# Cannabis_Humidity_2021-02-28.net
KiCad netlist of a schematic drawn in EasyEDA
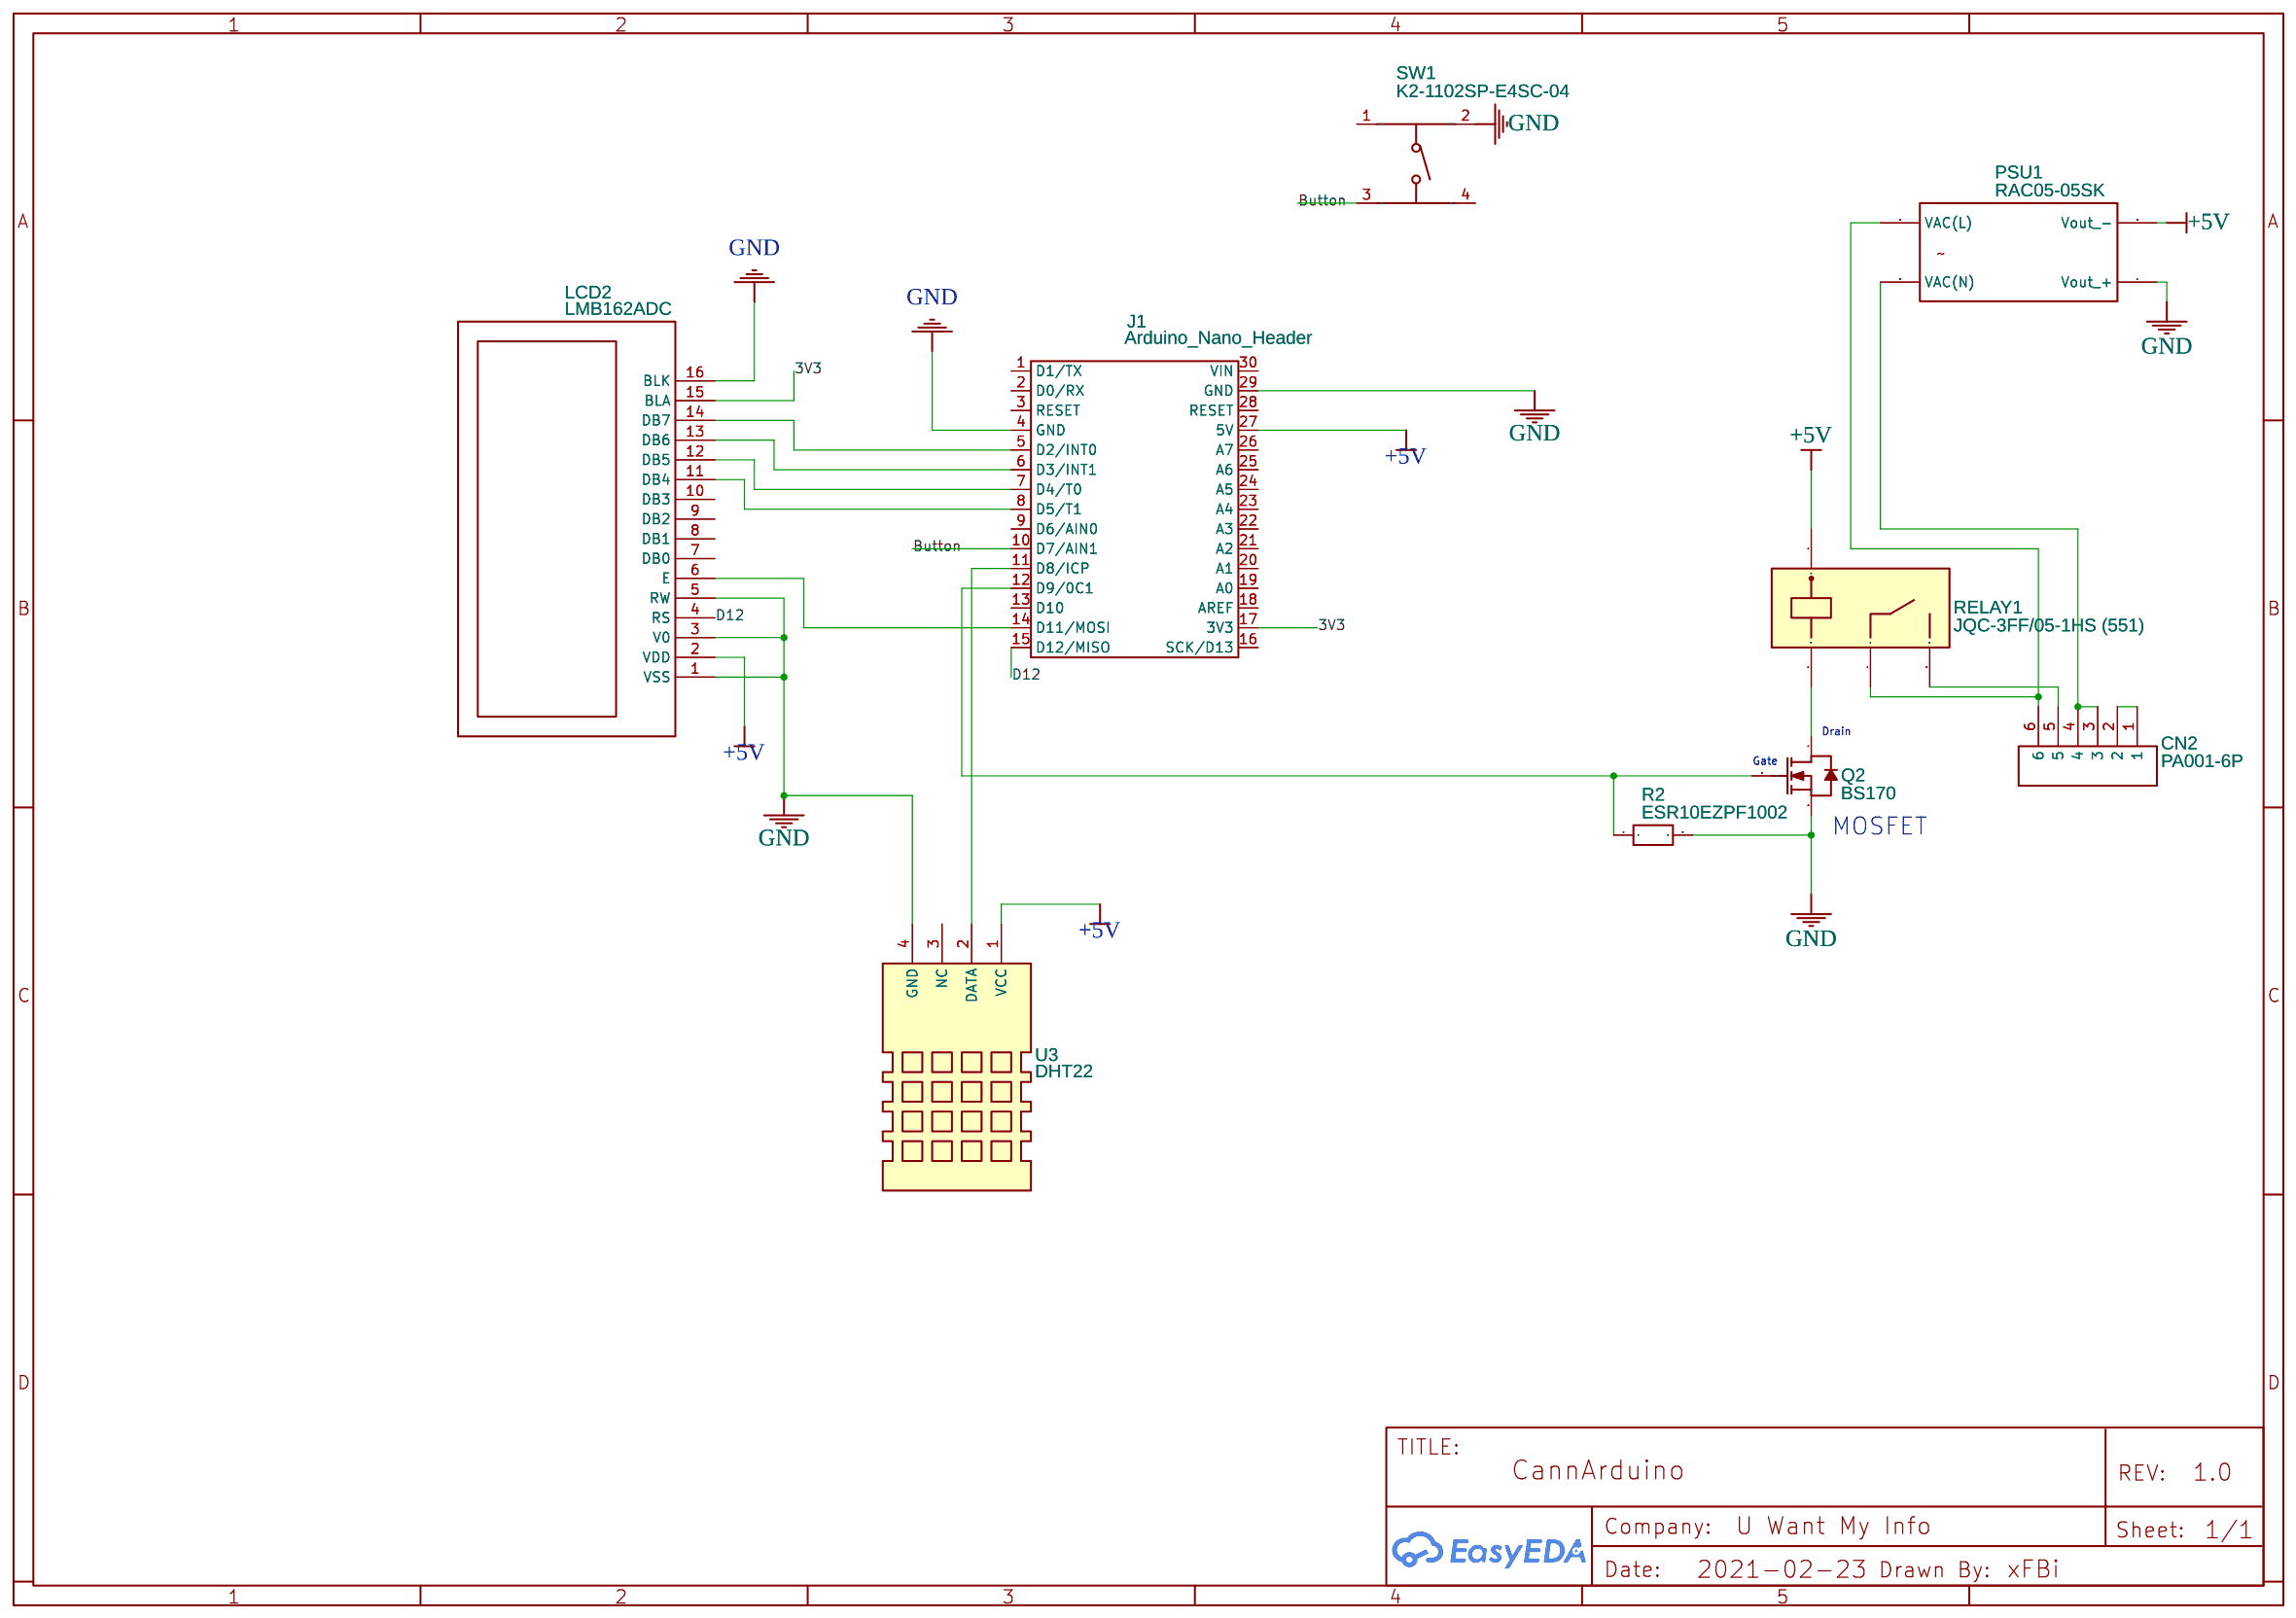
[diagram p0: schematic sheet]

(export (version "E")
  (design (tool "Eeschema 10.0.6"))
  (components
    (comp (ref "CN2")
      (value "PA001-6P")
      (fields (field (name "BOM_Supplier Part") "C173288"))
      (libsource (lib "") (part "PA001-6P"))
    )
    (comp (ref "J1") (value "Arduino_Nano_Header") (libsource (lib "") (part "Arduino_Nano_Header")))
    (comp (ref "LCD2")
      (value "LMB162ADC")
      (fields (field (name "BOM_Supplier Part") "C9741"))
      (libsource (lib "") (part "LMB162ADC"))
    )
    (comp (ref "PSU1")
      (value "RAC05-05SK")
      (fields (field (name "BOM_Supplier Part") "919-RAC05-05SK"))
      (libsource (lib "") (part "RAC05-05SK"))
    )
    (comp (ref "Q2")
      (value "BS170")
      (fields (field (name "BOM_Supplier Part") "C111691"))
      (libsource (lib "") (part "BS170"))
    )
    (comp (ref "R2")
      (value "ESR10EZPF1002")
      (fields (field (name "BOM_Supplier Part") "C510098"))
      (libsource (lib "") (part "ESR10EZPF1002"))
    )
    (comp (ref "RELAY1")
      (value "JQC-3FF/05-1HS (551)")
      (fields (field (name "BOM_Supplier Part") "C9224"))
      (libsource (lib "") (part "JQC-3FF/05-1HS (551)"))
    )
    (comp (ref "SW1")
      (value "K2-1102SP-E4SC-04")
      (fields (field (name "BOM_Supplier Part") "C136669"))
      (libsource (lib "") (part "K2-1102SP-E4SC-04"))
    )
    (comp (ref "U3")
      (value "DHT22")
      (fields (field (name "BOM_Supplier Part") "PRODUCT ID: 385"))
      (libsource (lib "") (part "DHT22"))
    )
  )
  (nets
    (net (code "1") (name "+5V") (class "Default")
      (node (ref "J1") (pin "27") (pinfunction "5V_27") (pintype "unspecified"))
      (node (ref "LCD2") (pin "2") (pinfunction "VDD_2") (pintype "unspecified"))
      (node (ref "PSU1") (pin "5") (pinfunction "Vout_-_5") (pintype "output"))
      (node (ref "RELAY1") (pin "1") (pinfunction "1_1") (pintype "input"))
      (node (ref "U3") (pin "1") (pinfunction "VCC_1") (pintype "unspecified"))
    )
    (net (code "2") (name "/3V3") (class "Default")
      (node (ref "J1") (pin "17") (pinfunction "3V3_17") (pintype "unspecified"))
      (node (ref "LCD2") (pin "15") (pinfunction "BLA_15") (pintype "unspecified"))
    )
    (net (code "3") (name "/Button") (class "Default")
      (node (ref "J1") (pin "10") (pinfunction "D7/AIN1_10") (pintype "unspecified"))
      (node (ref "SW1") (pin "3") (pinfunction "3_3") (pintype "unspecified"))
    )
    (net (code "4") (name "/D12") (class "Default")
      (node (ref "J1") (pin "15") (pinfunction "D12/MISO_15") (pintype "unspecified"))
      (node (ref "LCD2") (pin "4") (pinfunction "RS_4") (pintype "unspecified"))
    )
    (net (code "5") (name "GND") (class "Default")
      (node (ref "J1") (pin "29") (pinfunction "GND_29") (pintype "unspecified"))
      (node (ref "J1") (pin "4") (pinfunction "GND_4") (pintype "unspecified"))
      (node (ref "LCD2") (pin "1") (pinfunction "VSS_1") (pintype "unspecified"))
      (node (ref "LCD2") (pin "16") (pinfunction "BLK_16") (pintype "unspecified"))
      (node (ref "LCD2") (pin "3") (pinfunction "V0_3") (pintype "unspecified"))
      (node (ref "LCD2") (pin "5") (pinfunction "RW_5") (pintype "unspecified"))
      (node (ref "PSU1") (pin "4") (pinfunction "Vout_+_4") (pintype "output"))
      (node (ref "Q2") (pin "3") (pinfunction "S_3") (pintype "unspecified"))
      (node (ref "R2") (pin "2") (pinfunction "2_2") (pintype "unspecified"))
      (node (ref "SW1") (pin "2") (pinfunction "2_2") (pintype "unspecified"))
      (node (ref "U3") (pin "4") (pinfunction "GND_4") (pintype "unspecified"))
    )
    (net (code "6") (name "Net-(CN2-Pad1)") (class "Default")
      (node (ref "CN2") (pin "1") (pinfunction "1_1") (pintype "unspecified"))
      (node (ref "CN2") (pin "2") (pinfunction "2_2") (pintype "unspecified"))
    )
    (net (code "7") (name "Net-(CN2-Pad5)") (class "Default")
      (node (ref "CN2") (pin "5") (pinfunction "5_5") (pintype "unspecified"))
      (node (ref "RELAY1") (pin "3") (pinfunction "3_3") (pintype "input"))
    )
    (net (code "8") (name "Net-(J1-D2{slash}INT0)") (class "Default")
      (node (ref "J1") (pin "5") (pinfunction "D2/INT0_5") (pintype "unspecified"))
      (node (ref "LCD2") (pin "14") (pinfunction "DB7_14") (pintype "unspecified"))
    )
    (net (code "9") (name "Net-(J1-D3{slash}INT1)") (class "Default")
      (node (ref "J1") (pin "6") (pinfunction "D3/INT1_6") (pintype "unspecified"))
      (node (ref "LCD2") (pin "13") (pinfunction "DB6_13") (pintype "unspecified"))
    )
    (net (code "10") (name "Net-(J1-D4{slash}T0)") (class "Default")
      (node (ref "J1") (pin "7") (pinfunction "D4/T0_7") (pintype "unspecified"))
      (node (ref "LCD2") (pin "12") (pinfunction "DB5_12") (pintype "unspecified"))
    )
    (net (code "11") (name "Net-(J1-D5{slash}T1)") (class "Default")
      (node (ref "J1") (pin "8") (pinfunction "D5/T1_8") (pintype "unspecified"))
      (node (ref "LCD2") (pin "11") (pinfunction "DB4_11") (pintype "unspecified"))
    )
    (net (code "12") (name "Net-(J1-D8{slash}ICP)") (class "Default")
      (node (ref "J1") (pin "11") (pinfunction "D8/ICP_11") (pintype "unspecified"))
      (node (ref "U3") (pin "2") (pinfunction "DATA_2") (pintype "unspecified"))
    )
    (net (code "13") (name "Net-(J1-D9{slash}0C1)") (class "Default")
      (node (ref "J1") (pin "12") (pinfunction "D9/0C1_12") (pintype "unspecified"))
      (node (ref "Q2") (pin "2") (pinfunction "G_2") (pintype "unspecified"))
      (node (ref "R2") (pin "1") (pinfunction "1_1") (pintype "unspecified"))
    )
    (net (code "14") (name "Net-(J1-D11{slash}MOSI)") (class "Default")
      (node (ref "J1") (pin "14") (pinfunction "D11/MOSI_14") (pintype "unspecified"))
      (node (ref "LCD2") (pin "6") (pinfunction "E_6") (pintype "unspecified"))
    )
    (net (code "15") (name "Net-(PSU1-VAC(L))") (class "Default")
      (node (ref "CN2") (pin "6") (pinfunction "6_6") (pintype "unspecified"))
      (node (ref "PSU1") (pin "1") (pinfunction "VAC(L)_1") (pintype "input"))
      (node (ref "RELAY1") (pin "4") (pinfunction "4_4") (pintype "input"))
    )
    (net (code "16") (name "Net-(PSU1-VAC(N))") (class "Default")
      (node (ref "CN2") (pin "3") (pinfunction "3_3") (pintype "unspecified"))
      (node (ref "CN2") (pin "4") (pinfunction "4_4") (pintype "unspecified"))
      (node (ref "PSU1") (pin "2") (pinfunction "VAC(N)_2") (pintype "input"))
    )
    (net (code "17") (name "Net-(Q2-D)") (class "Default")
      (node (ref "Q2") (pin "1") (pinfunction "D_1") (pintype "unspecified"))
      (node (ref "RELAY1") (pin "2") (pinfunction "2_2") (pintype "input"))
    )
    (net (code "18") (name "unconnected-(J1-A0-Pad19)") (class "Default")
      (node (ref "J1") (pin "19") (pinfunction "A0_19") (pintype "unspecified"))
    )
    (net (code "19") (name "unconnected-(J1-A1-Pad20)") (class "Default")
      (node (ref "J1") (pin "20") (pinfunction "A1_20") (pintype "unspecified"))
    )
    (net (code "20") (name "unconnected-(J1-A2-Pad21)") (class "Default")
      (node (ref "J1") (pin "21") (pinfunction "A2_21") (pintype "unspecified"))
    )
    (net (code "21") (name "unconnected-(J1-A3-Pad22)") (class "Default")
      (node (ref "J1") (pin "22") (pinfunction "A3_22") (pintype "unspecified"))
    )
    (net (code "22") (name "unconnected-(J1-A4-Pad23)") (class "Default")
      (node (ref "J1") (pin "23") (pinfunction "A4_23") (pintype "unspecified"))
    )
    (net (code "23") (name "unconnected-(J1-A5-Pad24)") (class "Default")
      (node (ref "J1") (pin "24") (pinfunction "A5_24") (pintype "unspecified"))
    )
    (net (code "24") (name "unconnected-(J1-A6-Pad25)") (class "Default")
      (node (ref "J1") (pin "25") (pinfunction "A6_25") (pintype "unspecified"))
    )
    (net (code "25") (name "unconnected-(J1-A7-Pad26)") (class "Default")
      (node (ref "J1") (pin "26") (pinfunction "A7_26") (pintype "unspecified"))
    )
    (net (code "26") (name "unconnected-(J1-AREF-Pad18)") (class "Default")
      (node (ref "J1") (pin "18") (pinfunction "AREF_18") (pintype "unspecified"))
    )
    (net (code "27") (name "unconnected-(J1-D0{slash}RX-Pad2)") (class "Default")
      (node (ref "J1") (pin "2") (pinfunction "D0/RX_2") (pintype "unspecified"))
    )
    (net (code "28") (name "unconnected-(J1-D1{slash}TX-Pad1)") (class "Default")
      (node (ref "J1") (pin "1") (pinfunction "D1/TX_1") (pintype "unspecified"))
    )
    (net (code "29") (name "unconnected-(J1-D6{slash}AIN0-Pad9)") (class "Default")
      (node (ref "J1") (pin "9") (pinfunction "D6/AIN0_9") (pintype "unspecified"))
    )
    (net (code "30") (name "unconnected-(J1-D10-Pad13)") (class "Default")
      (node (ref "J1") (pin "13") (pinfunction "D10_13") (pintype "unspecified"))
    )
    (net (code "31") (name "unconnected-(J1-RESET-Pad3)") (class "Default")
      (node (ref "J1") (pin "3") (pinfunction "RESET_3") (pintype "unspecified"))
    )
    (net (code "32") (name "unconnected-(J1-RESET-Pad28)") (class "Default")
      (node (ref "J1") (pin "28") (pinfunction "RESET_28") (pintype "unspecified"))
    )
    (net (code "33") (name "unconnected-(J1-SCK{slash}D13-Pad16)") (class "Default")
      (node (ref "J1") (pin "16") (pinfunction "SCK/D13_16") (pintype "unspecified"))
    )
    (net (code "34") (name "unconnected-(J1-VIN-Pad30)") (class "Default")
      (node (ref "J1") (pin "30") (pinfunction "VIN_30") (pintype "unspecified"))
    )
    (net (code "35") (name "unconnected-(LCD2-DB0-Pad7)") (class "Default")
      (node (ref "LCD2") (pin "7") (pinfunction "DB0_7") (pintype "unspecified"))
    )
    (net (code "36") (name "unconnected-(LCD2-DB1-Pad8)") (class "Default")
      (node (ref "LCD2") (pin "8") (pinfunction "DB1_8") (pintype "unspecified"))
    )
    (net (code "37") (name "unconnected-(LCD2-DB2-Pad9)") (class "Default")
      (node (ref "LCD2") (pin "9") (pinfunction "DB2_9") (pintype "unspecified"))
    )
    (net (code "38") (name "unconnected-(LCD2-DB3-Pad10)") (class "Default")
      (node (ref "LCD2") (pin "10") (pinfunction "DB3_10") (pintype "unspecified"))
    )
    (net (code "39") (name "unconnected-(SW1-Pad1)") (class "Default")
      (node (ref "SW1") (pin "1") (pinfunction "1_1") (pintype "unspecified"))
    )
    (net (code "40") (name "unconnected-(SW1-Pad4)") (class "Default")
      (node (ref "SW1") (pin "4") (pinfunction "4_4") (pintype "unspecified"))
    )
    (net (code "41") (name "unconnected-(U3-NC-Pad3)") (class "Default")
      (node (ref "U3") (pin "3") (pinfunction "NC_3") (pintype "unspecified"))
    )
  )
)
